# SPI.net
KiCad netlist of a schematic drawn in EAGLE
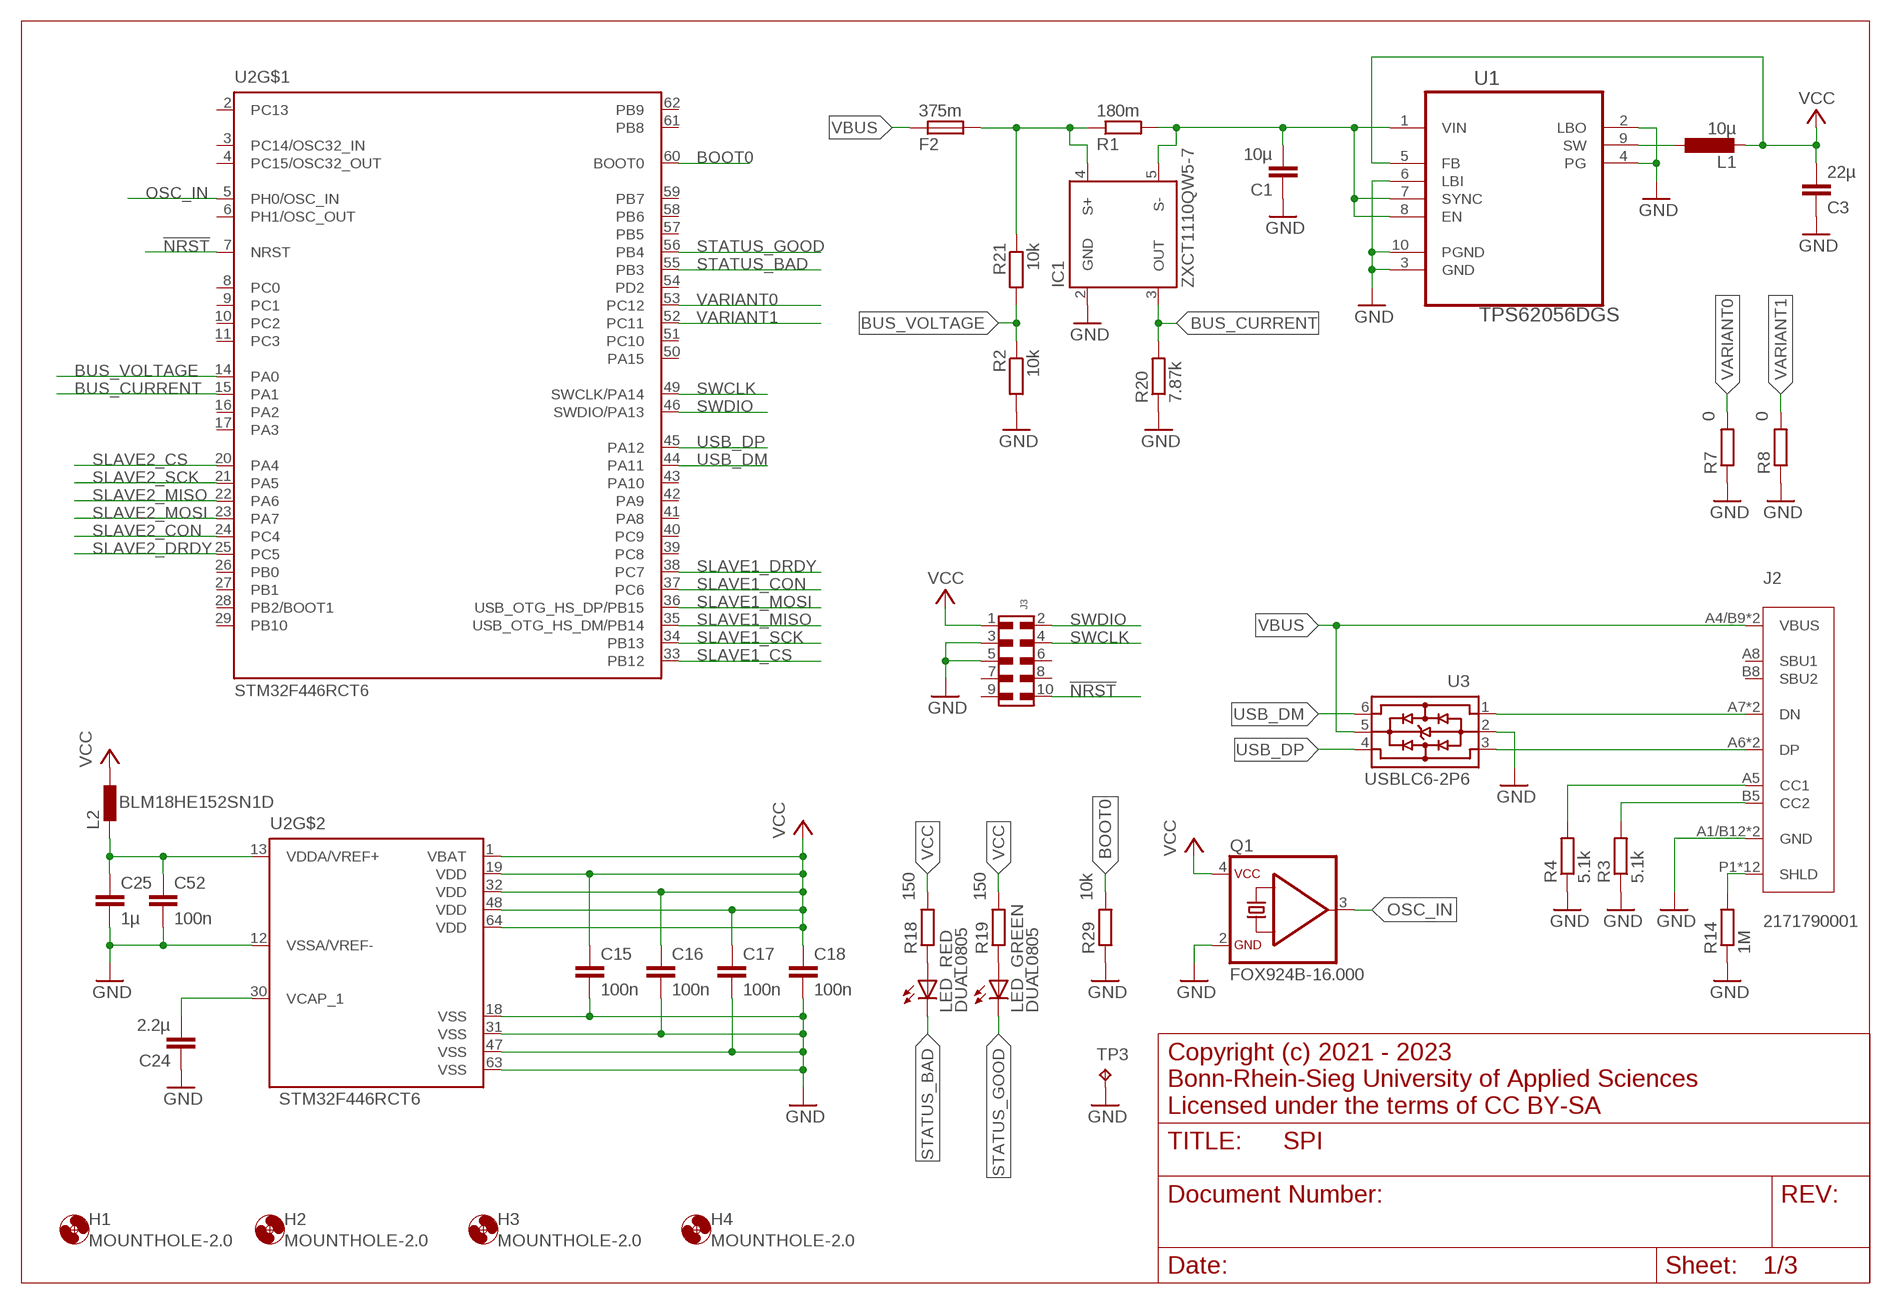
[diagram p0: schematic, sheet 1]
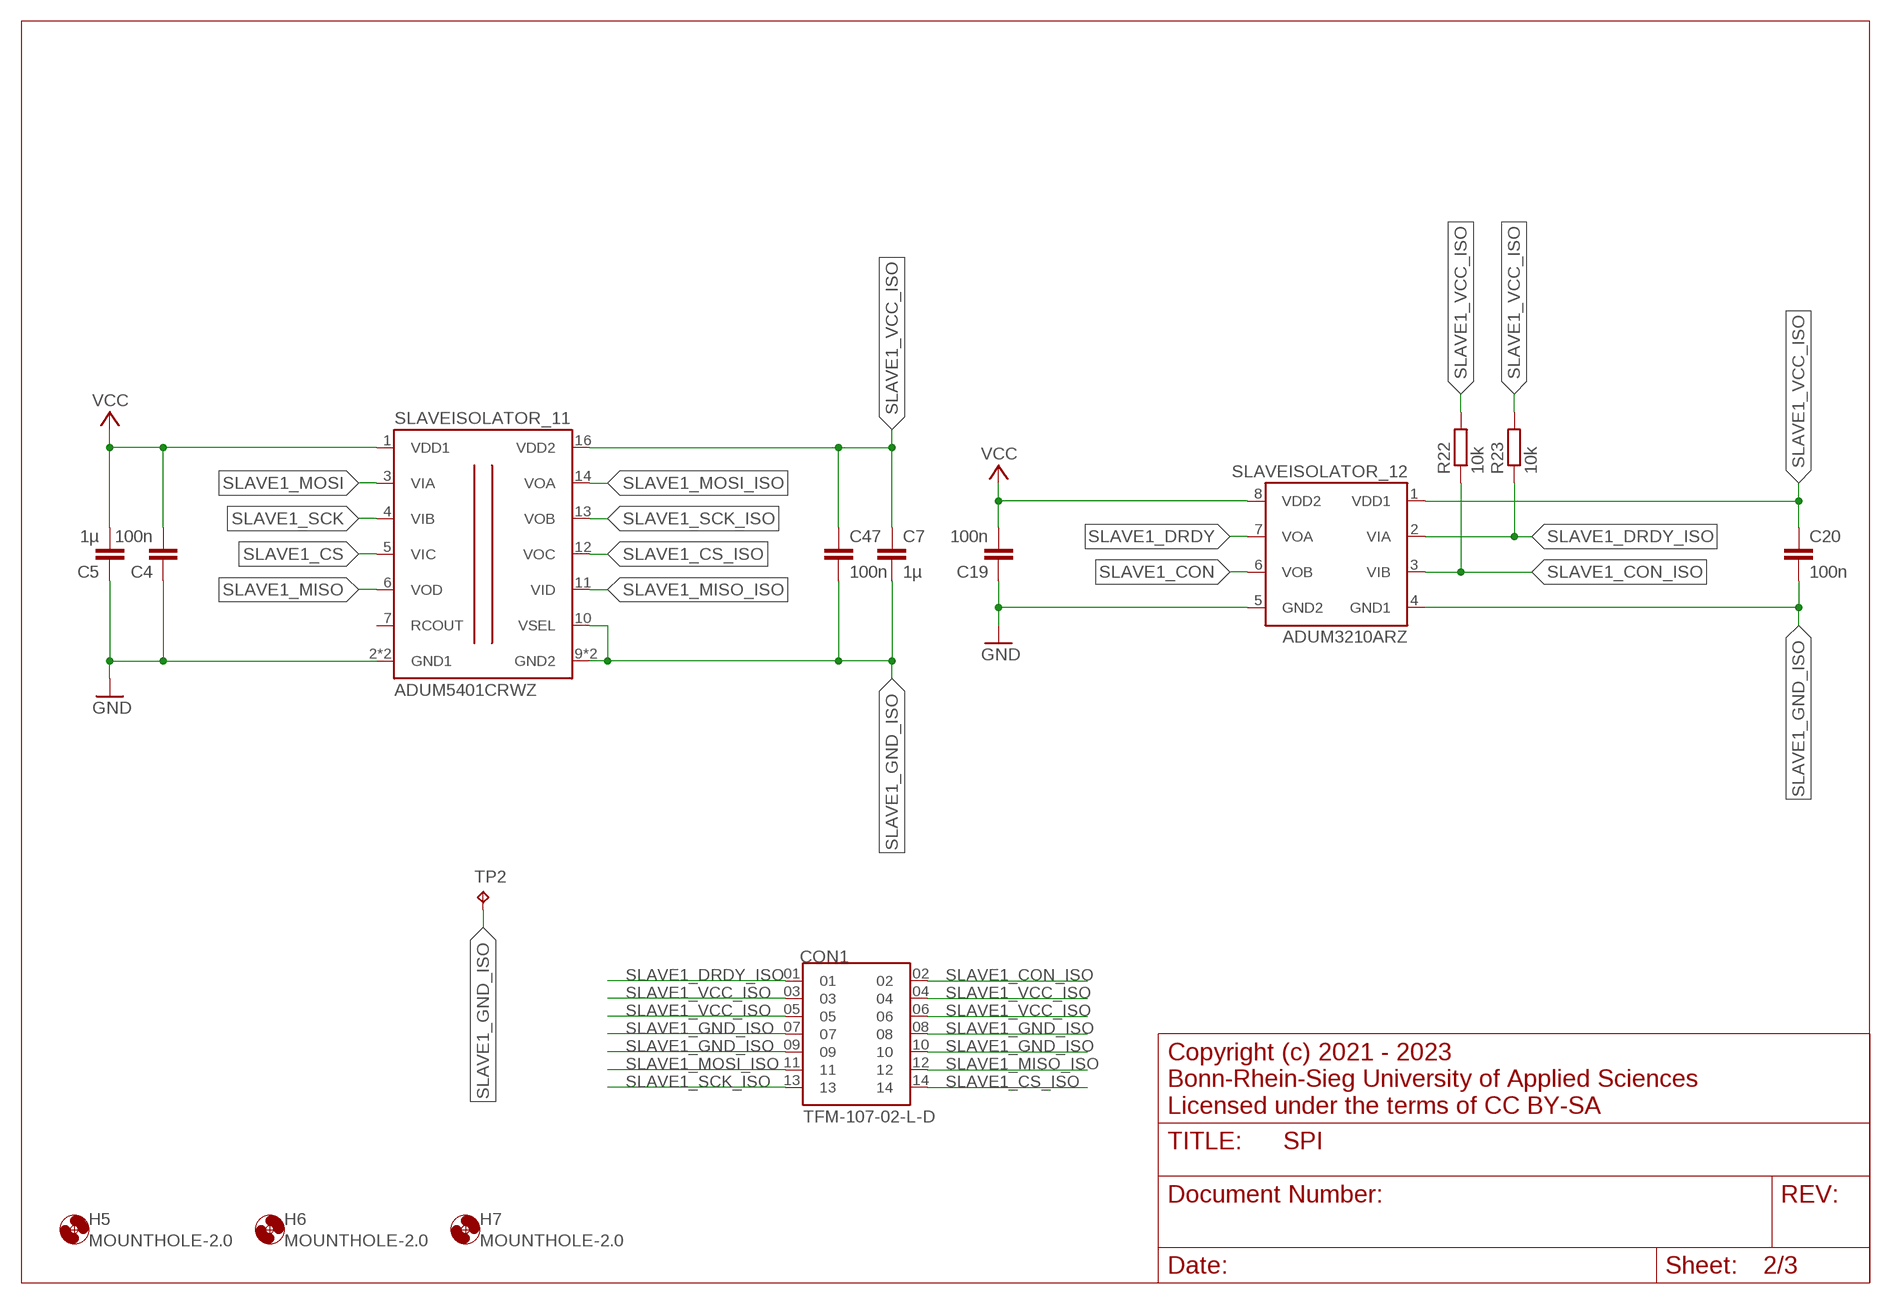
[diagram p1: schematic, sheet 2]
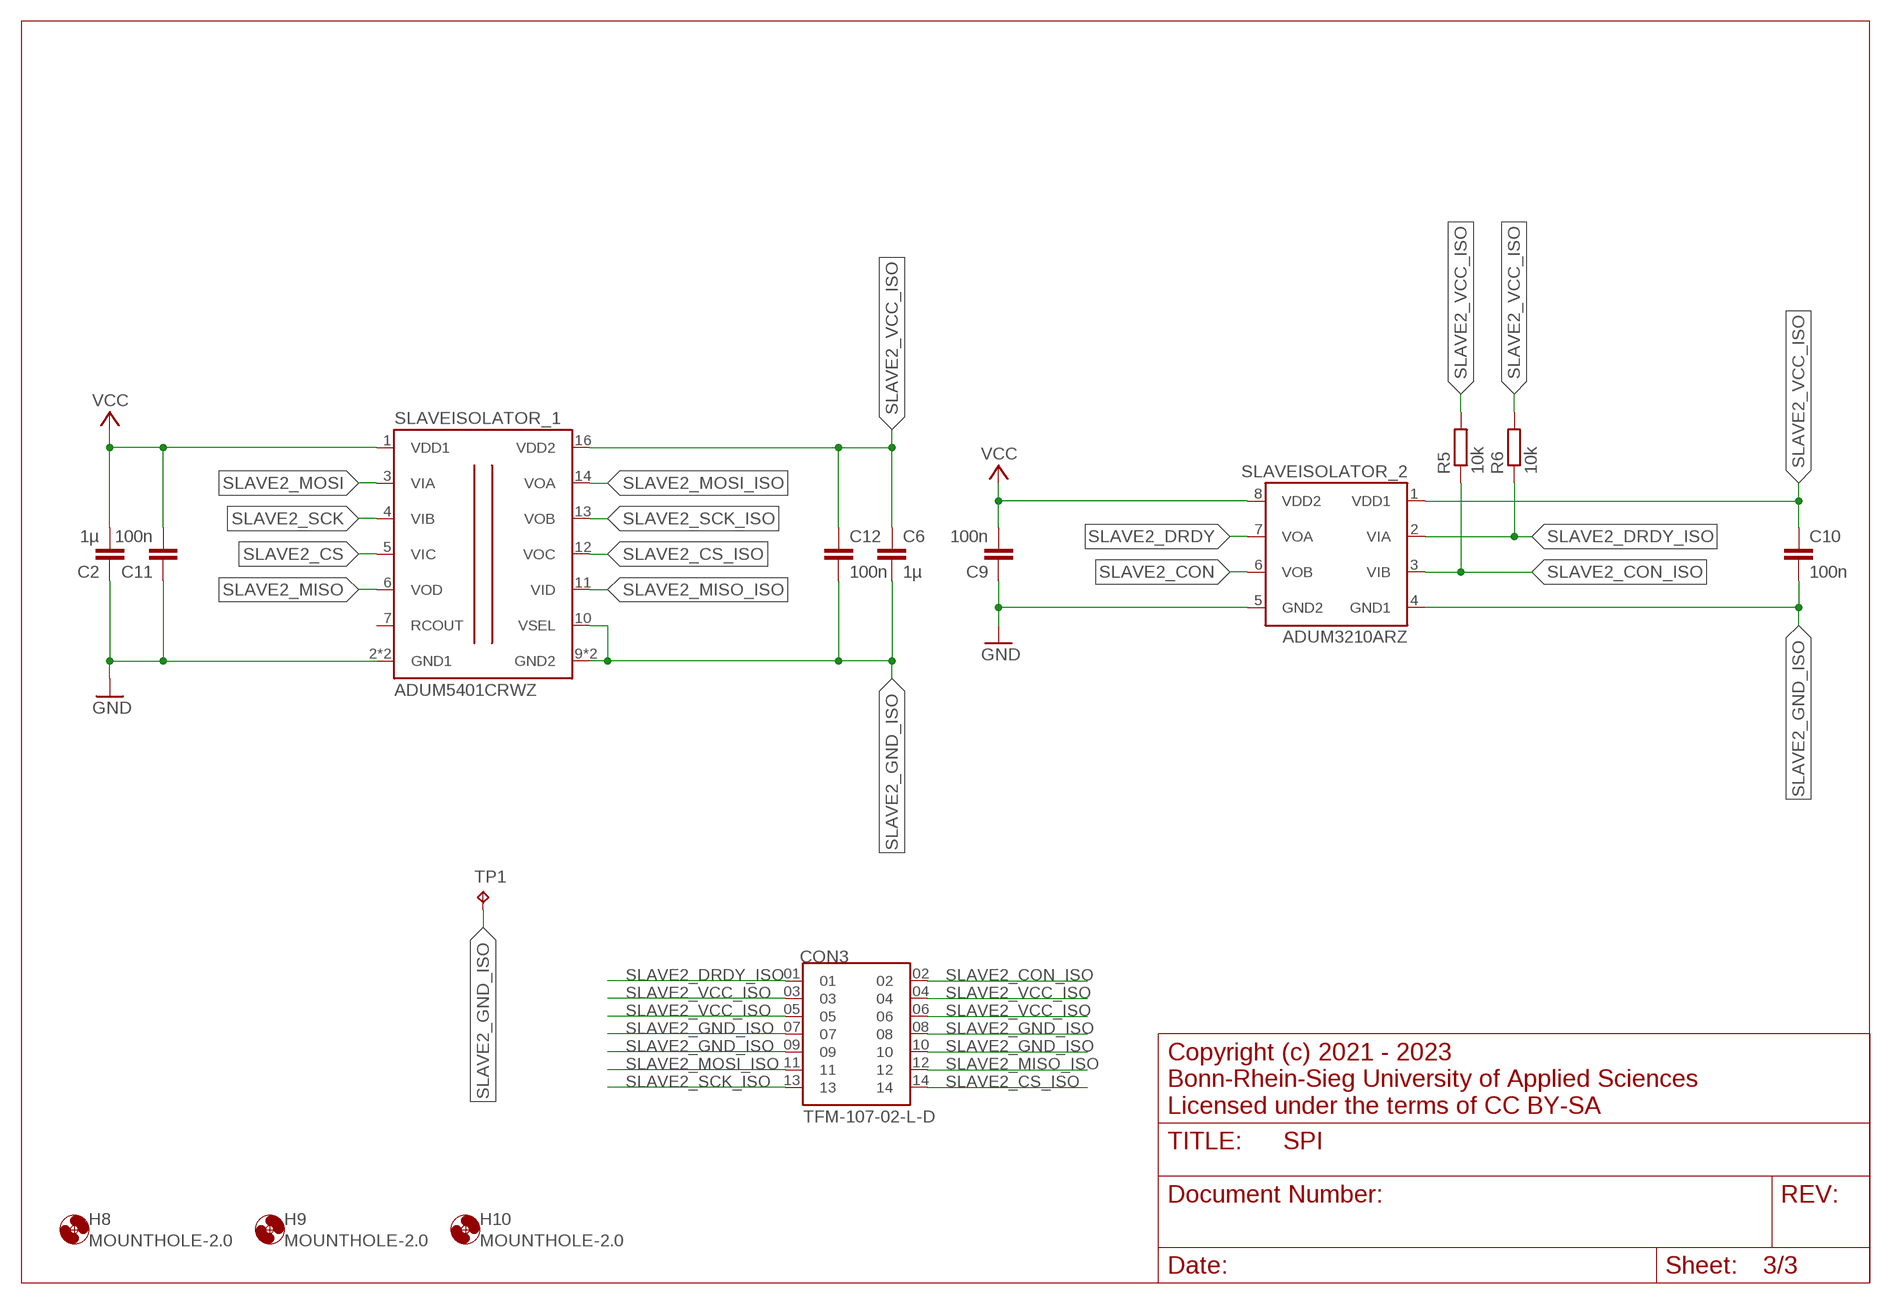
[diagram p2: schematic, sheet 3]

(export (version "E")
  (design (tool "Eeschema 10.0.6"))
  (components
    (comp (ref "C2")
      (value "1µ")
      (footprint "eagle-import:C0603")
      (libsource (lib "eagle-import") (part "C-EUC0603"))
    )
    (comp (ref "C6")
      (value "1µ")
      (footprint "eagle-import:C0603")
      (libsource (lib "eagle-import") (part "C-EUC0603"))
    )
    (comp (ref "C9")
      (value "100n")
      (footprint "eagle-import:C0603")
      (libsource (lib "eagle-import") (part "C-EUC0603"))
    )
    (comp (ref "C10")
      (value "100n")
      (footprint "eagle-import:C0603")
      (libsource (lib "eagle-import") (part "C-EUC0603"))
    )
    (comp (ref "C11")
      (value "100n")
      (footprint "eagle-import:C0603")
      (libsource (lib "eagle-import") (part "C-EUC0603"))
    )
    (comp (ref "C12")
      (value "100n")
      (footprint "eagle-import:C0603")
      (libsource (lib "eagle-import") (part "C-EUC0603"))
    )
    (comp (ref "CON3")
      (value "TFM-107-02-L-D")
      (footprint "eagle-import:SAMTEC_TFM-107-02-L-D")
      (fields (field (name "DIGI-KEY_PART_NUMBER") "SAM14682TR-ND") (field (name "MF") "Samtec"))
      (libsource (lib "eagle-import") (part "TFM-107-02-L-D"))
    )
    (comp (ref "H8")
      (value "MOUNTHOLE-2.0")
      (footprint "eagle-import:2.0")
      (libsource (lib "eagle-import") (part "MOUNTHOLE-2.0"))
    )
    (comp (ref "H9")
      (value "MOUNTHOLE-2.0")
      (footprint "eagle-import:2.0")
      (libsource (lib "eagle-import") (part "MOUNTHOLE-2.0"))
    )
    (comp (ref "H10")
      (value "MOUNTHOLE-2.0")
      (footprint "eagle-import:2.0")
      (libsource (lib "eagle-import") (part "MOUNTHOLE-2.0"))
    )
    (comp (ref "R5")
      (value "10k")
      (footprint "eagle-import:R0603")
      (libsource (lib "eagle-import") (part "R-EU_R0603"))
    )
    (comp (ref "R6")
      (value "10k")
      (footprint "eagle-import:R0603")
      (libsource (lib "eagle-import") (part "R-EU_R0603"))
    )
    (comp (ref "SLAVEISOLATOR_1")
      (value "ADUM5401CRWZ")
      (footprint "eagle-import:SO16W")
      (libsource (lib "eagle-import") (part "ADUM5401RWZC"))
    )
    (comp (ref "SLAVEISOLATOR_2")
      (value "ADUM3210ARZ")
      (footprint "eagle-import:SOIC8")
      (libsource (lib "eagle-import") (part "ADUM3210RZA"))
    )
    (comp (ref "TP1")
      (value "TP3.8X2.03")
      (footprint "eagle-import:3.8X2.03")
      (libsource (lib "eagle-import") (part "TP3.8X2.03"))
    )
    (comp (ref "C1")
      (value "10µ")
      (footprint "eagle-import:C0603")
      (libsource (lib "eagle-import") (part "rcl_334_C-EUC0603"))
    )
    (comp (ref "C3")
      (value "22µ")
      (footprint "eagle-import:C0603")
      (libsource (lib "eagle-import") (part "rcl_334_C-EUC0603"))
    )
    (comp (ref "C15")
      (value "100n")
      (footprint "eagle-import:C0603")
      (libsource (lib "eagle-import") (part "C-EUC0603"))
    )
    (comp (ref "C16")
      (value "100n")
      (footprint "eagle-import:C0603")
      (libsource (lib "eagle-import") (part "C-EUC0603"))
    )
    (comp (ref "C17")
      (value "100n")
      (footprint "eagle-import:C0603")
      (libsource (lib "eagle-import") (part "C-EUC0603"))
    )
    (comp (ref "C18")
      (value "100n")
      (footprint "eagle-import:C0603")
      (libsource (lib "eagle-import") (part "C-EUC0603"))
    )
    (comp (ref "C24")
      (value "2.2µ")
      (footprint "eagle-import:C0603")
      (libsource (lib "eagle-import") (part "C-EUC0603"))
    )
    (comp (ref "C25")
      (value "1µ")
      (footprint "eagle-import:C0603")
      (libsource (lib "eagle-import") (part "C-EUC0603"))
    )
    (comp (ref "C52")
      (value "100n")
      (footprint "eagle-import:C0603")
      (libsource (lib "eagle-import") (part "C-EUC0603"))
    )
    (comp (ref "F2")
      (value "375m")
      (footprint "eagle-import:R0603")
      (libsource (lib "eagle-import") (part "FUSE0603"))
    )
    (comp (ref "H1")
      (value "MOUNTHOLE-2.0")
      (footprint "eagle-import:2.0")
      (libsource (lib "eagle-import") (part "MOUNTHOLE-2.0"))
    )
    (comp (ref "H2")
      (value "MOUNTHOLE-2.0")
      (footprint "eagle-import:2.0")
      (libsource (lib "eagle-import") (part "MOUNTHOLE-2.0"))
    )
    (comp (ref "H3")
      (value "MOUNTHOLE-2.0")
      (footprint "eagle-import:2.0")
      (libsource (lib "eagle-import") (part "MOUNTHOLE-2.0"))
    )
    (comp (ref "H4")
      (value "MOUNTHOLE-2.0")
      (footprint "eagle-import:2.0")
      (libsource (lib "eagle-import") (part "MOUNTHOLE-2.0"))
    )
    (comp (ref "IC1")
      (value "ZXCT1110QW5-7")
      (footprint "eagle-import:SOT23-5L")
      (libsource (lib "eagle-import") (part "ZXCT1110QW5-7"))
    )
    (comp (ref "J2")
      (value "2171790001")
      (footprint "eagle-import:2171790001_MOL")
      (fields (field (name "COPYRIGHT") "Copyright (C) 2021 Ultra Librarian. All rights reserved."))
      (libsource (lib "eagle-import") (part "2171790001"))
    )
    (comp (ref "J3")
      (value "6210XX21021_62101021021")
      (footprint "eagle-import:62101021021")
      (libsource (lib "eagle-import") (part "6210XX21021_62101021021"))
    )
    (comp (ref "L1")
      (value "10µ")
      (footprint "eagle-import:2SMD")
      (libsource (lib "eagle-import") (part "VLS3012E?-T100M"))
    )
    (comp (ref "L2")
      (value "BLM18HE152SN1D")
      (footprint "eagle-import:0603")
      (libsource (lib "eagle-import") (part "BLM18HE152SN1D"))
    )
    (comp (ref "LED_")
      (value "DUAL0805")
      (footprint "eagle-import:CHIPLEDX2")
      (libsource (lib "eagle-import") (part "DUAL0805"))
    )
    (comp (ref "Q1")
      (value "FOX924B-16.000")
      (footprint "eagle-import:FOX924B")
      (libsource (lib "eagle-import") (part "FOX924B-16.000"))
    )
    (comp (ref "R1")
      (value "180m")
      (footprint "eagle-import:R0603")
      (libsource (lib "eagle-import") (part "rcl_334_R-EU_R0603"))
    )
    (comp (ref "R2")
      (value "10k")
      (footprint "eagle-import:R0603")
      (libsource (lib "eagle-import") (part "rcl_334_R-EU_R0603"))
    )
    (comp (ref "R3")
      (value "5.1k")
      (footprint "eagle-import:R0603")
      (libsource (lib "eagle-import") (part "rcl_334_R-EU_R0603"))
    )
    (comp (ref "R4")
      (value "5.1k")
      (footprint "eagle-import:R0603")
      (libsource (lib "eagle-import") (part "rcl_334_R-EU_R0603"))
    )
    (comp (ref "R7")
      (value "0")
      (footprint "eagle-import:R0603")
      (libsource (lib "eagle-import") (part "R-EU_R0603"))
    )
    (comp (ref "R8")
      (value "0")
      (footprint "eagle-import:R0603")
      (libsource (lib "eagle-import") (part "R-EU_R0603"))
    )
    (comp (ref "R14")
      (value "1M")
      (footprint "eagle-import:R0603")
      (libsource (lib "eagle-import") (part "rcl_334_R-EU_R0603"))
    )
    (comp (ref "R18")
      (value "150")
      (footprint "eagle-import:R0603")
      (libsource (lib "eagle-import") (part "R-EU_R0603"))
    )
    (comp (ref "R19")
      (value "150")
      (footprint "eagle-import:R0603")
      (libsource (lib "eagle-import") (part "R-EU_R0603"))
    )
    (comp (ref "R20")
      (value "7.87k")
      (footprint "eagle-import:R0603")
      (libsource (lib "eagle-import") (part "rcl_334_R-EU_R0603"))
    )
    (comp (ref "R21")
      (value "10k")
      (footprint "eagle-import:R0603")
      (libsource (lib "eagle-import") (part "rcl_334_R-EU_R0603"))
    )
    (comp (ref "R29")
      (value "10k")
      (footprint "eagle-import:R0603")
      (libsource (lib "eagle-import") (part "R-EU_R0603"))
    )
    (comp (ref "TP3")
      (value "TP3.8X2.03")
      (footprint "eagle-import:3.8X2.03")
      (libsource (lib "eagle-import") (part "TP3.8X2.03"))
    )
    (comp (ref "U1")
      (value "TPS62056DGS")
      (footprint "eagle-import:SOP50P490X110-10N")
      (libsource (lib "eagle-import") (part "TPS62056DGS"))
    )
    (comp (ref "U2")
      (value "STM32F446RCT6")
      (footprint "eagle-import:LQFP64")
      (libsource (lib "eagle-import") (part "STM32F446R?T6C"))
    )
    (comp (ref "U3")
      (value "USBLC6-2P6")
      (footprint "eagle-import:SOT-666")
      (libsource (lib "eagle-import") (part "USBLC6-2P6"))
    )
    (comp (ref "C4")
      (value "100n")
      (footprint "eagle-import:C0603")
      (libsource (lib "eagle-import") (part "C-EUC0603"))
    )
    (comp (ref "C5")
      (value "1µ")
      (footprint "eagle-import:C0603")
      (libsource (lib "eagle-import") (part "C-EUC0603"))
    )
    (comp (ref "C7")
      (value "1µ")
      (footprint "eagle-import:C0603")
      (libsource (lib "eagle-import") (part "C-EUC0603"))
    )
    (comp (ref "C19")
      (value "100n")
      (footprint "eagle-import:C0603")
      (libsource (lib "eagle-import") (part "C-EUC0603"))
    )
    (comp (ref "C20")
      (value "100n")
      (footprint "eagle-import:C0603")
      (libsource (lib "eagle-import") (part "C-EUC0603"))
    )
    (comp (ref "C47")
      (value "100n")
      (footprint "eagle-import:C0603")
      (libsource (lib "eagle-import") (part "C-EUC0603"))
    )
    (comp (ref "CON1")
      (value "TFM-107-02-L-D")
      (footprint "eagle-import:SAMTEC_TFM-107-02-L-D")
      (fields (field (name "DIGI-KEY_PART_NUMBER") "SAM14682TR-ND") (field (name "MF") "Samtec"))
      (libsource (lib "eagle-import") (part "TFM-107-02-L-D"))
    )
    (comp (ref "H5")
      (value "MOUNTHOLE-2.0")
      (footprint "eagle-import:2.0")
      (libsource (lib "eagle-import") (part "MOUNTHOLE-2.0"))
    )
    (comp (ref "H6")
      (value "MOUNTHOLE-2.0")
      (footprint "eagle-import:2.0")
      (libsource (lib "eagle-import") (part "MOUNTHOLE-2.0"))
    )
    (comp (ref "H7")
      (value "MOUNTHOLE-2.0")
      (footprint "eagle-import:2.0")
      (libsource (lib "eagle-import") (part "MOUNTHOLE-2.0"))
    )
    (comp (ref "R22")
      (value "10k")
      (footprint "eagle-import:R0603")
      (libsource (lib "eagle-import") (part "R-EU_R0603"))
    )
    (comp (ref "R23")
      (value "10k")
      (footprint "eagle-import:R0603")
      (libsource (lib "eagle-import") (part "R-EU_R0603"))
    )
    (comp (ref "SLAVEISOLATOR_11")
      (value "ADUM5401CRWZ")
      (footprint "eagle-import:SO16W")
      (libsource (lib "eagle-import") (part "ADUM5401RWZC"))
    )
    (comp (ref "SLAVEISOLATOR_12")
      (value "ADUM3210ARZ")
      (footprint "eagle-import:SOIC8")
      (libsource (lib "eagle-import") (part "ADUM3210RZA"))
    )
    (comp (ref "TP2")
      (value "TP3.8X2.03")
      (footprint "eagle-import:3.8X2.03")
      (libsource (lib "eagle-import") (part "TP3.8X2.03"))
    )
  )
  (nets
    (net (code "1") (name "BOOT0") (class "Default")
      (node (ref "R29") (pin "2") (pinfunction "2_2") (pintype "passive"))
      (node (ref "U2") (pin "60") (pinfunction "BOOT0_60") (pintype "bidirectional"))
    )
    (net (code "2") (name "BUS_CURRENT") (class "Default")
      (node (ref "IC1") (pin "3") (pinfunction "OUT_3") (pintype "output"))
      (node (ref "R20") (pin "2") (pinfunction "2_2") (pintype "passive"))
      (node (ref "U2") (pin "15") (pinfunction "PA1_15") (pintype "bidirectional"))
    )
    (net (code "3") (name "BUS_VOLTAGE") (class "Default")
      (node (ref "R2") (pin "1") (pinfunction "1_1") (pintype "passive"))
      (node (ref "R21") (pin "2") (pinfunction "2_2") (pintype "passive"))
      (node (ref "U2") (pin "14") (pinfunction "PA0_14") (pintype "bidirectional"))
    )
    (net (code "4") (name "GND") (class "Default")
      (node (ref "C1") (pin "1") (pinfunction "1_1") (pintype "passive"))
      (node (ref "C11") (pin "1") (pinfunction "1_1") (pintype "passive"))
      (node (ref "C15") (pin "2") (pinfunction "2_2") (pintype "passive"))
      (node (ref "C16") (pin "2") (pinfunction "2_2") (pintype "passive"))
      (node (ref "C17") (pin "2") (pinfunction "2_2") (pintype "passive"))
      (node (ref "C18") (pin "2") (pinfunction "2_2") (pintype "passive"))
      (node (ref "C19") (pin "1") (pinfunction "1_1") (pintype "passive"))
      (node (ref "C2") (pin "1") (pinfunction "1_1") (pintype "passive"))
      (node (ref "C24") (pin "1") (pinfunction "1_1") (pintype "passive"))
      (node (ref "C25") (pin "2") (pinfunction "2_2") (pintype "passive"))
      (node (ref "C3") (pin "1") (pinfunction "1_1") (pintype "passive"))
      (node (ref "C4") (pin "1") (pinfunction "1_1") (pintype "passive"))
      (node (ref "C5") (pin "1") (pinfunction "1_1") (pintype "passive"))
      (node (ref "C52") (pin "2") (pinfunction "2_2") (pintype "passive"))
      (node (ref "C9") (pin "1") (pinfunction "1_1") (pintype "passive"))
      (node (ref "IC1") (pin "2") (pinfunction "GND_2") (pintype "power_in"))
      (node (ref "J2") (pin "A1/B12") (pinfunction "GND_A1/B12") (pintype "passive"))
      (node (ref "J2") (pin "B1/A12") (pinfunction "GND_B1/A12") (pintype "passive"))
      (node (ref "J3") (pin "3") (pinfunction "3_3") (pintype "passive"))
      (node (ref "J3") (pin "5") (pinfunction "5_5") (pintype "passive"))
      (node (ref "Q1") (pin "2") (pinfunction "GND_2") (pintype "power_in"))
      (node (ref "R14") (pin "1") (pinfunction "1_1") (pintype "passive"))
      (node (ref "R2") (pin "2") (pinfunction "2_2") (pintype "passive"))
      (node (ref "R20") (pin "1") (pinfunction "1_1") (pintype "passive"))
      (node (ref "R29") (pin "1") (pinfunction "1_1") (pintype "passive"))
      (node (ref "R3") (pin "1") (pinfunction "1_1") (pintype "passive"))
      (node (ref "R4") (pin "1") (pinfunction "1_1") (pintype "passive"))
      (node (ref "R7") (pin "1") (pinfunction "1_1") (pintype "passive"))
      (node (ref "R8") (pin "1") (pinfunction "1_1") (pintype "passive"))
      (node (ref "SLAVEISOLATOR_1") (pin "2") (pinfunction "GND1_2") (pintype "bidirectional"))
      (node (ref "SLAVEISOLATOR_1") (pin "8") (pinfunction "GND1_8") (pintype "bidirectional"))
      (node (ref "SLAVEISOLATOR_11") (pin "2") (pinfunction "GND1_2") (pintype "bidirectional"))
      (node (ref "SLAVEISOLATOR_11") (pin "8") (pinfunction "GND1_8") (pintype "bidirectional"))
      (node (ref "SLAVEISOLATOR_12") (pin "5") (pinfunction "GND2_5") (pintype "bidirectional"))
      (node (ref "SLAVEISOLATOR_2") (pin "5") (pinfunction "GND2_5") (pintype "bidirectional"))
      (node (ref "TP3") (pin "TP") (pinfunction "TP_TP") (pintype "input"))
      (node (ref "U1") (pin "10") (pinfunction "PGND_10") (pintype "passive"))
      (node (ref "U1") (pin "2") (pinfunction "LBO_2") (pintype "bidirectional"))
      (node (ref "U1") (pin "3") (pinfunction "GND_3") (pintype "passive"))
      (node (ref "U1") (pin "4") (pinfunction "PG_4") (pintype "bidirectional"))
      (node (ref "U1") (pin "6") (pinfunction "LBI_6") (pintype "input"))
      (node (ref "U2") (pin "12") (pinfunction "VSSA/VREF-_12") (pintype "bidirectional"))
      (node (ref "U2") (pin "18") (pinfunction "VSS_18") (pintype "bidirectional"))
      (node (ref "U2") (pin "31") (pinfunction "VSS_31") (pintype "bidirectional"))
      (node (ref "U2") (pin "47") (pinfunction "VSS_47") (pintype "bidirectional"))
      (node (ref "U2") (pin "63") (pinfunction "VSS_63") (pintype "bidirectional"))
      (node (ref "U3") (pin "2") (pinfunction "2_2") (pintype "passive"))
    )
    (net (code "5") (name "Net-(IC1-S+)") (class "Default")
      (node (ref "F2") (pin "2") (pinfunction "2_2") (pintype "passive"))
      (node (ref "IC1") (pin "4") (pinfunction "S+_4") (pintype "input"))
      (node (ref "R1") (pin "1") (pinfunction "1_1") (pintype "passive"))
      (node (ref "R21") (pin "1") (pinfunction "1_1") (pintype "passive"))
    )
    (net (code "6") (name "Net-(IC1-S-)") (class "Default")
      (node (ref "C1") (pin "2") (pinfunction "2_2") (pintype "passive"))
      (node (ref "IC1") (pin "5") (pinfunction "S-_5") (pintype "input"))
      (node (ref "R1") (pin "2") (pinfunction "2_2") (pintype "passive"))
      (node (ref "U1") (pin "1") (pinfunction "VIN_1") (pintype "power_in"))
      (node (ref "U1") (pin "7") (pinfunction "SYNC_7") (pintype "input"))
      (node (ref "U1") (pin "8") (pinfunction "EN_8") (pintype "input"))
    )
    (net (code "7") (name "Net-(J2-CC1)") (class "Default")
      (node (ref "J2") (pin "A5") (pinfunction "CC1_A5") (pintype "bidirectional"))
      (node (ref "R4") (pin "2") (pinfunction "2_2") (pintype "passive"))
    )
    (net (code "8") (name "Net-(J2-CC2)") (class "Default")
      (node (ref "J2") (pin "B5") (pinfunction "CC2_B5") (pintype "bidirectional"))
      (node (ref "R3") (pin "2") (pinfunction "2_2") (pintype "passive"))
    )
    (net (code "9") (name "Net-(J2-DN-PadA7)") (class "Default")
      (node (ref "J2") (pin "A7") (pinfunction "DN_A7") (pintype "bidirectional"))
      (node (ref "J2") (pin "B7") (pinfunction "DN_B7") (pintype "bidirectional"))
      (node (ref "U3") (pin "1") (pinfunction "1_1") (pintype "bidirectional"))
    )
    (net (code "10") (name "Net-(J2-DP-PadA6)") (class "Default")
      (node (ref "J2") (pin "A6") (pinfunction "DP_A6") (pintype "bidirectional"))
      (node (ref "J2") (pin "B6") (pinfunction "DP_B6") (pintype "bidirectional"))
      (node (ref "U3") (pin "3") (pinfunction "3_3") (pintype "bidirectional"))
    )
    (net (code "11") (name "Net-(J2-SHLD-PadP1)") (class "Default")
      (node (ref "J2") (pin "P1") (pinfunction "SHLD_P1") (pintype "bidirectional"))
      (node (ref "J2") (pin "P2") (pinfunction "SHLD_P2") (pintype "bidirectional"))
      (node (ref "J2") (pin "P3") (pinfunction "SHLD_P3") (pintype "bidirectional"))
      (node (ref "J2") (pin "P4") (pinfunction "SHLD_P4") (pintype "bidirectional"))
      (node (ref "J2") (pin "S1") (pinfunction "SHLD_S1") (pintype "bidirectional"))
      (node (ref "J2") (pin "S2") (pinfunction "SHLD_S2") (pintype "bidirectional"))
      (node (ref "J2") (pin "S3") (pinfunction "SHLD_S3") (pintype "bidirectional"))
      (node (ref "J2") (pin "S4") (pinfunction "SHLD_S4") (pintype "bidirectional"))
      (node (ref "J2") (pin "S5") (pinfunction "SHLD_S5") (pintype "bidirectional"))
      (node (ref "J2") (pin "S6") (pinfunction "SHLD_S6") (pintype "bidirectional"))
      (node (ref "J2") (pin "S7") (pinfunction "SHLD_S7") (pintype "bidirectional"))
      (node (ref "J2") (pin "S8") (pinfunction "SHLD_S8") (pintype "bidirectional"))
      (node (ref "R14") (pin "2") (pinfunction "2_2") (pintype "passive"))
    )
    (net (code "12") (name "Net-(L1-1)") (class "Default")
      (node (ref "L1") (pin "P$1") (pinfunction "1_P$1") (pintype "passive"))
      (node (ref "U1") (pin "9") (pinfunction "SW_9") (pintype "output"))
    )
    (net (code "13") (name "Net-(LED_A-A)") (class "Default")
      (node (ref "LED_") (pin "A2") (pinfunction "A_A2") (pintype "passive"))
      (node (ref "R19") (pin "1") (pinfunction "1_1") (pintype "passive"))
    )
    (net (code "14") (name "Net-(LED_B-A)") (class "Default")
      (node (ref "LED_") (pin "A1") (pinfunction "A_A1") (pintype "passive"))
      (node (ref "R18") (pin "1") (pinfunction "1_1") (pintype "passive"))
    )
    (net (code "15") (name "Net-(U2B-VCAP_1)") (class "Default")
      (node (ref "C24") (pin "2") (pinfunction "2_2") (pintype "passive"))
      (node (ref "U2") (pin "30") (pinfunction "VCAP_1_30") (pintype "bidirectional"))
    )
    (net (code "16") (name "Net-(U2B-VDDA{slash}VREF+)") (class "Default")
      (node (ref "C25") (pin "1") (pinfunction "1_1") (pintype "passive"))
      (node (ref "C52") (pin "1") (pinfunction "1_1") (pintype "passive"))
      (node (ref "L2") (pin "2") (pinfunction "2_2") (pintype "passive"))
      (node (ref "U2") (pin "13") (pinfunction "VDDA/VREF+_13") (pintype "bidirectional"))
    )
    (net (code "17") (name "OSC_IN") (class "Default")
      (node (ref "Q1") (pin "3") (pinfunction "OUT_3") (pintype "output"))
      (node (ref "U2") (pin "5") (pinfunction "PH0/OSC_IN_5") (pintype "bidirectional"))
    )
    (net (code "18") (name "SLAVE1_CON") (class "Default")
      (node (ref "SLAVEISOLATOR_12") (pin "6") (pinfunction "VOB_6") (pintype "bidirectional"))
      (node (ref "U2") (pin "37") (pinfunction "PC6_37") (pintype "bidirectional"))
    )
    (net (code "19") (name "SLAVE1_CON_ISO") (class "Default")
      (node (ref "CON1") (pin "02") (pinfunction "02_02") (pintype "passive"))
      (node (ref "R22") (pin "1") (pinfunction "1_1") (pintype "passive"))
      (node (ref "SLAVEISOLATOR_12") (pin "3") (pinfunction "VIB_3") (pintype "bidirectional"))
    )
    (net (code "20") (name "SLAVE1_CS") (class "Default")
      (node (ref "SLAVEISOLATOR_11") (pin "5") (pinfunction "VIC_5") (pintype "bidirectional"))
      (node (ref "U2") (pin "33") (pinfunction "PB12_33") (pintype "bidirectional"))
    )
    (net (code "21") (name "SLAVE1_CS_ISO") (class "Default")
      (node (ref "CON1") (pin "14") (pinfunction "14_14") (pintype "passive"))
      (node (ref "SLAVEISOLATOR_11") (pin "12") (pinfunction "VOC_12") (pintype "bidirectional"))
    )
    (net (code "22") (name "SLAVE1_DRDY") (class "Default")
      (node (ref "SLAVEISOLATOR_12") (pin "7") (pinfunction "VOA_7") (pintype "bidirectional"))
      (node (ref "U2") (pin "38") (pinfunction "PC7_38") (pintype "bidirectional"))
    )
    (net (code "23") (name "SLAVE1_DRDY_ISO") (class "Default")
      (node (ref "CON1") (pin "01") (pinfunction "01_01") (pintype "passive"))
      (node (ref "R23") (pin "1") (pinfunction "1_1") (pintype "passive"))
      (node (ref "SLAVEISOLATOR_12") (pin "2") (pinfunction "VIA_2") (pintype "bidirectional"))
    )
    (net (code "24") (name "SLAVE1_GND_ISO") (class "Default")
      (node (ref "C20") (pin "2") (pinfunction "2_2") (pintype "passive"))
      (node (ref "C47") (pin "2") (pinfunction "2_2") (pintype "passive"))
      (node (ref "C7") (pin "2") (pinfunction "2_2") (pintype "passive"))
      (node (ref "CON1") (pin "07") (pinfunction "07_07") (pintype "passive"))
      (node (ref "CON1") (pin "08") (pinfunction "08_08") (pintype "passive"))
      (node (ref "CON1") (pin "09") (pinfunction "09_09") (pintype "passive"))
      (node (ref "CON1") (pin "10") (pinfunction "10_10") (pintype "passive"))
      (node (ref "SLAVEISOLATOR_11") (pin "10") (pinfunction "VSEL_10") (pintype "bidirectional"))
      (node (ref "SLAVEISOLATOR_11") (pin "15") (pinfunction "GND2_15") (pintype "bidirectional"))
      (node (ref "SLAVEISOLATOR_11") (pin "9") (pinfunction "GND2_9") (pintype "bidirectional"))
      (node (ref "SLAVEISOLATOR_12") (pin "4") (pinfunction "GND1_4") (pintype "bidirectional"))
      (node (ref "TP2") (pin "TP") (pinfunction "TP_TP") (pintype "input"))
    )
    (net (code "25") (name "SLAVE1_MISO") (class "Default")
      (node (ref "SLAVEISOLATOR_11") (pin "6") (pinfunction "VOD_6") (pintype "bidirectional"))
      (node (ref "U2") (pin "35") (pinfunction "USB_OTG_HS_DM/PB14_35") (pintype "bidirectional"))
    )
    (net (code "26") (name "SLAVE1_MISO_ISO") (class "Default")
      (node (ref "CON1") (pin "12") (pinfunction "12_12") (pintype "passive"))
      (node (ref "SLAVEISOLATOR_11") (pin "11") (pinfunction "VID_11") (pintype "bidirectional"))
    )
    (net (code "27") (name "SLAVE1_MOSI") (class "Default")
      (node (ref "SLAVEISOLATOR_11") (pin "3") (pinfunction "VIA_3") (pintype "bidirectional"))
      (node (ref "U2") (pin "36") (pinfunction "USB_OTG_HS_DP/PB15_36") (pintype "bidirectional"))
    )
    (net (code "28") (name "SLAVE1_MOSI_ISO") (class "Default")
      (node (ref "CON1") (pin "11") (pinfunction "11_11") (pintype "passive"))
      (node (ref "SLAVEISOLATOR_11") (pin "14") (pinfunction "VOA_14") (pintype "bidirectional"))
    )
    (net (code "29") (name "SLAVE1_SCK") (class "Default")
      (node (ref "SLAVEISOLATOR_11") (pin "4") (pinfunction "VIB_4") (pintype "bidirectional"))
      (node (ref "U2") (pin "34") (pinfunction "PB13_34") (pintype "bidirectional"))
    )
    (net (code "30") (name "SLAVE1_SCK_ISO") (class "Default")
      (node (ref "CON1") (pin "13") (pinfunction "13_13") (pintype "passive"))
      (node (ref "SLAVEISOLATOR_11") (pin "13") (pinfunction "VOB_13") (pintype "bidirectional"))
    )
    (net (code "31") (name "SLAVE1_VCC_ISO") (class "Default")
      (node (ref "C20") (pin "1") (pinfunction "1_1") (pintype "passive"))
      (node (ref "C47") (pin "1") (pinfunction "1_1") (pintype "passive"))
      (node (ref "C7") (pin "1") (pinfunction "1_1") (pintype "passive"))
      (node (ref "CON1") (pin "03") (pinfunction "03_03") (pintype "passive"))
      (node (ref "CON1") (pin "04") (pinfunction "04_04") (pintype "passive"))
      (node (ref "CON1") (pin "05") (pinfunction "05_05") (pintype "passive"))
      (node (ref "CON1") (pin "06") (pinfunction "06_06") (pintype "passive"))
      (node (ref "R22") (pin "2") (pinfunction "2_2") (pintype "passive"))
      (node (ref "R23") (pin "2") (pinfunction "2_2") (pintype "passive"))
      (node (ref "SLAVEISOLATOR_11") (pin "16") (pinfunction "VDD2_16") (pintype "bidirectional"))
      (node (ref "SLAVEISOLATOR_12") (pin "1") (pinfunction "VDD1_1") (pintype "bidirectional"))
    )
    (net (code "32") (name "SLAVE2_CON") (class "Default")
      (node (ref "SLAVEISOLATOR_2") (pin "6") (pinfunction "VOB_6") (pintype "bidirectional"))
      (node (ref "U2") (pin "24") (pinfunction "PC4_24") (pintype "bidirectional"))
    )
    (net (code "33") (name "SLAVE2_CON_ISO") (class "Default")
      (node (ref "CON3") (pin "02") (pinfunction "02_02") (pintype "passive"))
      (node (ref "R5") (pin "1") (pinfunction "1_1") (pintype "passive"))
      (node (ref "SLAVEISOLATOR_2") (pin "3") (pinfunction "VIB_3") (pintype "bidirectional"))
    )
    (net (code "34") (name "SLAVE2_CS") (class "Default")
      (node (ref "SLAVEISOLATOR_1") (pin "5") (pinfunction "VIC_5") (pintype "bidirectional"))
      (node (ref "U2") (pin "20") (pinfunction "PA4_20") (pintype "bidirectional"))
    )
    (net (code "35") (name "SLAVE2_CS_ISO") (class "Default")
      (node (ref "CON3") (pin "14") (pinfunction "14_14") (pintype "passive"))
      (node (ref "SLAVEISOLATOR_1") (pin "12") (pinfunction "VOC_12") (pintype "bidirectional"))
    )
    (net (code "36") (name "SLAVE2_DRDY") (class "Default")
      (node (ref "SLAVEISOLATOR_2") (pin "7") (pinfunction "VOA_7") (pintype "bidirectional"))
      (node (ref "U2") (pin "25") (pinfunction "PC5_25") (pintype "bidirectional"))
    )
    (net (code "37") (name "SLAVE2_DRDY_ISO") (class "Default")
      (node (ref "CON3") (pin "01") (pinfunction "01_01") (pintype "passive"))
      (node (ref "R6") (pin "1") (pinfunction "1_1") (pintype "passive"))
      (node (ref "SLAVEISOLATOR_2") (pin "2") (pinfunction "VIA_2") (pintype "bidirectional"))
    )
    (net (code "38") (name "SLAVE2_GND_ISO") (class "Default")
      (node (ref "C10") (pin "2") (pinfunction "2_2") (pintype "passive"))
      (node (ref "C12") (pin "2") (pinfunction "2_2") (pintype "passive"))
      (node (ref "C6") (pin "2") (pinfunction "2_2") (pintype "passive"))
      (node (ref "CON3") (pin "07") (pinfunction "07_07") (pintype "passive"))
      (node (ref "CON3") (pin "08") (pinfunction "08_08") (pintype "passive"))
      (node (ref "CON3") (pin "09") (pinfunction "09_09") (pintype "passive"))
      (node (ref "CON3") (pin "10") (pinfunction "10_10") (pintype "passive"))
      (node (ref "SLAVEISOLATOR_1") (pin "10") (pinfunction "VSEL_10") (pintype "bidirectional"))
      (node (ref "SLAVEISOLATOR_1") (pin "15") (pinfunction "GND2_15") (pintype "bidirectional"))
      (node (ref "SLAVEISOLATOR_1") (pin "9") (pinfunction "GND2_9") (pintype "bidirectional"))
      (node (ref "SLAVEISOLATOR_2") (pin "4") (pinfunction "GND1_4") (pintype "bidirectional"))
      (node (ref "TP1") (pin "TP") (pinfunction "TP_TP") (pintype "input"))
    )
    (net (code "39") (name "SLAVE2_MISO") (class "Default")
      (node (ref "SLAVEISOLATOR_1") (pin "6") (pinfunction "VOD_6") (pintype "bidirectional"))
      (node (ref "U2") (pin "22") (pinfunction "PA6_22") (pintype "bidirectional"))
    )
    (net (code "40") (name "SLAVE2_MISO_ISO") (class "Default")
      (node (ref "CON3") (pin "12") (pinfunction "12_12") (pintype "passive"))
      (node (ref "SLAVEISOLATOR_1") (pin "11") (pinfunction "VID_11") (pintype "bidirectional"))
    )
    (net (code "41") (name "SLAVE2_MOSI") (class "Default")
      (node (ref "SLAVEISOLATOR_1") (pin "3") (pinfunction "VIA_3") (pintype "bidirectional"))
      (node (ref "U2") (pin "23") (pinfunction "PA7_23") (pintype "bidirectional"))
    )
    (net (code "42") (name "SLAVE2_MOSI_ISO") (class "Default")
      (node (ref "CON3") (pin "11") (pinfunction "11_11") (pintype "passive"))
      (node (ref "SLAVEISOLATOR_1") (pin "14") (pinfunction "VOA_14") (pintype "bidirectional"))
    )
    (net (code "43") (name "SLAVE2_SCK") (class "Default")
      (node (ref "SLAVEISOLATOR_1") (pin "4") (pinfunction "VIB_4") (pintype "bidirectional"))
      (node (ref "U2") (pin "21") (pinfunction "PA5_21") (pintype "bidirectional"))
    )
    (net (code "44") (name "SLAVE2_SCK_ISO") (class "Default")
      (node (ref "CON3") (pin "13") (pinfunction "13_13") (pintype "passive"))
      (node (ref "SLAVEISOLATOR_1") (pin "13") (pinfunction "VOB_13") (pintype "bidirectional"))
    )
    (net (code "45") (name "SLAVE2_VCC_ISO") (class "Default")
      (node (ref "C10") (pin "1") (pinfunction "1_1") (pintype "passive"))
      (node (ref "C12") (pin "1") (pinfunction "1_1") (pintype "passive"))
      (node (ref "C6") (pin "1") (pinfunction "1_1") (pintype "passive"))
      (node (ref "CON3") (pin "03") (pinfunction "03_03") (pintype "passive"))
      (node (ref "CON3") (pin "04") (pinfunction "04_04") (pintype "passive"))
      (node (ref "CON3") (pin "05") (pinfunction "05_05") (pintype "passive"))
      (node (ref "CON3") (pin "06") (pinfunction "06_06") (pintype "passive"))
      (node (ref "R5") (pin "2") (pinfunction "2_2") (pintype "passive"))
      (node (ref "R6") (pin "2") (pinfunction "2_2") (pintype "passive"))
      (node (ref "SLAVEISOLATOR_1") (pin "16") (pinfunction "VDD2_16") (pintype "bidirectional"))
      (node (ref "SLAVEISOLATOR_2") (pin "1") (pinfunction "VDD1_1") (pintype "bidirectional"))
    )
    (net (code "46") (name "STATUS_BAD") (class "Default")
      (node (ref "LED_") (pin "C1") (pinfunction "C_C1") (pintype "passive"))
      (node (ref "U2") (pin "55") (pinfunction "PB3_55") (pintype "bidirectional"))
    )
    (net (code "47") (name "STATUS_GOOD") (class "Default")
      (node (ref "LED_") (pin "C2") (pinfunction "C_C2") (pintype "passive"))
      (node (ref "U2") (pin "56") (pinfunction "PB4_56") (pintype "bidirectional"))
    )
    (net (code "48") (name "SWCLK") (class "Default")
      (node (ref "J3") (pin "4") (pinfunction "4_4") (pintype "passive"))
      (node (ref "U2") (pin "49") (pinfunction "SWCLK/PA14_49") (pintype "bidirectional"))
    )
    (net (code "49") (name "SWDIO") (class "Default")
      (node (ref "J3") (pin "2") (pinfunction "2_2") (pintype "passive"))
      (node (ref "U2") (pin "46") (pinfunction "SWDIO/PA13_46") (pintype "bidirectional"))
    )
    (net (code "50") (name "USB_DM") (class "Default")
      (node (ref "U2") (pin "44") (pinfunction "PA11_44") (pintype "bidirectional"))
      (node (ref "U3") (pin "6") (pinfunction "6_6") (pintype "bidirectional"))
    )
    (net (code "51") (name "USB_DP") (class "Default")
      (node (ref "U2") (pin "45") (pinfunction "PA12_45") (pintype "bidirectional"))
      (node (ref "U3") (pin "4") (pinfunction "4_4") (pintype "bidirectional"))
    )
    (net (code "52") (name "VARIANT0") (class "Default")
      (node (ref "R7") (pin "2") (pinfunction "2_2") (pintype "passive"))
      (node (ref "U2") (pin "53") (pinfunction "PC12_53") (pintype "bidirectional"))
    )
    (net (code "53") (name "VARIANT1") (class "Default")
      (node (ref "R8") (pin "2") (pinfunction "2_2") (pintype "passive"))
      (node (ref "U2") (pin "52") (pinfunction "PC11_52") (pintype "bidirectional"))
    )
    (net (code "54") (name "VBUS") (class "Default")
      (node (ref "F2") (pin "1") (pinfunction "1_1") (pintype "passive"))
      (node (ref "J2") (pin "A4/B9") (pinfunction "VBUS_A4/B9") (pintype "power_in"))
      (node (ref "J2") (pin "B4/A9") (pinfunction "VBUS_B4/A9") (pintype "power_in"))
      (node (ref "U3") (pin "5") (pinfunction "5_5") (pintype "passive"))
    )
    (net (code "55") (name "VCC") (class "Default")
      (node (ref "C11") (pin "2") (pinfunction "2_2") (pintype "passive"))
      (node (ref "C15") (pin "1") (pinfunction "1_1") (pintype "passive"))
      (node (ref "C16") (pin "1") (pinfunction "1_1") (pintype "passive"))
      (node (ref "C17") (pin "1") (pinfunction "1_1") (pintype "passive"))
      (node (ref "C18") (pin "1") (pinfunction "1_1") (pintype "passive"))
      (node (ref "C19") (pin "2") (pinfunction "2_2") (pintype "passive"))
      (node (ref "C2") (pin "2") (pinfunction "2_2") (pintype "passive"))
      (node (ref "C3") (pin "2") (pinfunction "2_2") (pintype "passive"))
      (node (ref "C4") (pin "2") (pinfunction "2_2") (pintype "passive"))
      (node (ref "C5") (pin "2") (pinfunction "2_2") (pintype "passive"))
      (node (ref "C9") (pin "2") (pinfunction "2_2") (pintype "passive"))
      (node (ref "J3") (pin "1") (pinfunction "1_1") (pintype "passive"))
      (node (ref "L1") (pin "P$2") (pinfunction "2_P$2") (pintype "passive"))
      (node (ref "L2") (pin "1") (pinfunction "1_1") (pintype "passive"))
      (node (ref "Q1") (pin "4") (pinfunction "VCC_4") (pintype "power_in"))
      (node (ref "R18") (pin "2") (pinfunction "2_2") (pintype "passive"))
      (node (ref "R19") (pin "2") (pinfunction "2_2") (pintype "passive"))
      (node (ref "SLAVEISOLATOR_1") (pin "1") (pinfunction "VDD1_1") (pintype "bidirectional"))
      (node (ref "SLAVEISOLATOR_11") (pin "1") (pinfunction "VDD1_1") (pintype "bidirectional"))
      (node (ref "SLAVEISOLATOR_12") (pin "8") (pinfunction "VDD2_8") (pintype "bidirectional"))
      (node (ref "SLAVEISOLATOR_2") (pin "8") (pinfunction "VDD2_8") (pintype "bidirectional"))
      (node (ref "U1") (pin "5") (pinfunction "FB_5") (pintype "input"))
      (node (ref "U2") (pin "1") (pinfunction "VBAT_1") (pintype "bidirectional"))
      (node (ref "U2") (pin "19") (pinfunction "VDD_19") (pintype "bidirectional"))
      (node (ref "U2") (pin "32") (pinfunction "VDD_32") (pintype "bidirectional"))
      (node (ref "U2") (pin "48") (pinfunction "VDD_48") (pintype "bidirectional"))
      (node (ref "U2") (pin "64") (pinfunction "VDD_64") (pintype "bidirectional"))
    )
    (net (code "56") (name "unconnected-(J2-SBU1-PadA8)") (class "Default")
      (node (ref "J2") (pin "A8") (pinfunction "SBU1_A8") (pintype "bidirectional"))
    )
    (net (code "57") (name "unconnected-(J2-SBU2-PadB8)") (class "Default")
      (node (ref "J2") (pin "B8") (pinfunction "SBU2_B8") (pintype "bidirectional"))
    )
    (net (code "58") (name "unconnected-(J3-Pad6)") (class "Default")
      (node (ref "J3") (pin "6") (pinfunction "6_6") (pintype "passive"))
    )
    (net (code "59") (name "unconnected-(J3-Pad7)") (class "Default")
      (node (ref "J3") (pin "7") (pinfunction "7_7") (pintype "passive"))
    )
    (net (code "60") (name "unconnected-(J3-Pad8)") (class "Default")
      (node (ref "J3") (pin "8") (pinfunction "8_8") (pintype "passive"))
    )
    (net (code "61") (name "unconnected-(J3-Pad9)") (class "Default")
      (node (ref "J3") (pin "9") (pinfunction "9_9") (pintype "passive"))
    )
    (net (code "62") (name "unconnected-(SLAVEISOLATOR_1-RCOUT-Pad7)") (class "Default")
      (node (ref "SLAVEISOLATOR_1") (pin "7") (pinfunction "RCOUT_7") (pintype "bidirectional"))
    )
    (net (code "63") (name "unconnected-(SLAVEISOLATOR_11-RCOUT-Pad7)") (class "Default")
      (node (ref "SLAVEISOLATOR_11") (pin "7") (pinfunction "RCOUT_7") (pintype "bidirectional"))
    )
    (net (code "64") (name "unconnected-(U2A-PA2-Pad16)") (class "Default")
      (node (ref "U2") (pin "16") (pinfunction "PA2_16") (pintype "bidirectional"))
    )
    (net (code "65") (name "unconnected-(U2A-PA3-Pad17)") (class "Default")
      (node (ref "U2") (pin "17") (pinfunction "PA3_17") (pintype "bidirectional"))
    )
    (net (code "66") (name "unconnected-(U2A-PA8-Pad41)") (class "Default")
      (node (ref "U2") (pin "41") (pinfunction "PA8_41") (pintype "bidirectional"))
    )
    (net (code "67") (name "unconnected-(U2A-PA9-Pad42)") (class "Default")
      (node (ref "U2") (pin "42") (pinfunction "PA9_42") (pintype "bidirectional"))
    )
    (net (code "68") (name "unconnected-(U2A-PA10-Pad43)") (class "Default")
      (node (ref "U2") (pin "43") (pinfunction "PA10_43") (pintype "bidirectional"))
    )
    (net (code "69") (name "unconnected-(U2A-PA15-Pad50)") (class "Default")
      (node (ref "U2") (pin "50") (pinfunction "PA15_50") (pintype "bidirectional"))
    )
    (net (code "70") (name "unconnected-(U2A-PB0-Pad26)") (class "Default")
      (node (ref "U2") (pin "26") (pinfunction "PB0_26") (pintype "bidirectional"))
    )
    (net (code "71") (name "unconnected-(U2A-PB1-Pad27)") (class "Default")
      (node (ref "U2") (pin "27") (pinfunction "PB1_27") (pintype "bidirectional"))
    )
    (net (code "72") (name "unconnected-(U2A-PB2{slash}BOOT1-Pad28)") (class "Default")
      (node (ref "U2") (pin "28") (pinfunction "PB2/BOOT1_28") (pintype "bidirectional"))
    )
    (net (code "73") (name "unconnected-(U2A-PB5-Pad57)") (class "Default")
      (node (ref "U2") (pin "57") (pinfunction "PB5_57") (pintype "bidirectional"))
    )
    (net (code "74") (name "unconnected-(U2A-PB6-Pad58)") (class "Default")
      (node (ref "U2") (pin "58") (pinfunction "PB6_58") (pintype "bidirectional"))
    )
    (net (code "75") (name "unconnected-(U2A-PB7-Pad59)") (class "Default")
      (node (ref "U2") (pin "59") (pinfunction "PB7_59") (pintype "bidirectional"))
    )
    (net (code "76") (name "unconnected-(U2A-PB8-Pad61)") (class "Default")
      (node (ref "U2") (pin "61") (pinfunction "PB8_61") (pintype "bidirectional"))
    )
    (net (code "77") (name "unconnected-(U2A-PB9-Pad62)") (class "Default")
      (node (ref "U2") (pin "62") (pinfunction "PB9_62") (pintype "bidirectional"))
    )
    (net (code "78") (name "unconnected-(U2A-PB10-Pad29)") (class "Default")
      (node (ref "U2") (pin "29") (pinfunction "PB10_29") (pintype "bidirectional"))
    )
    (net (code "79") (name "unconnected-(U2A-PC0-Pad8)") (class "Default")
      (node (ref "U2") (pin "8") (pinfunction "PC0_8") (pintype "bidirectional"))
    )
    (net (code "80") (name "unconnected-(U2A-PC1-Pad9)") (class "Default")
      (node (ref "U2") (pin "9") (pinfunction "PC1_9") (pintype "bidirectional"))
    )
    (net (code "81") (name "unconnected-(U2A-PC2-Pad10)") (class "Default")
      (node (ref "U2") (pin "10") (pinfunction "PC2_10") (pintype "bidirectional"))
    )
    (net (code "82") (name "unconnected-(U2A-PC3-Pad11)") (class "Default")
      (node (ref "U2") (pin "11") (pinfunction "PC3_11") (pintype "bidirectional"))
    )
    (net (code "83") (name "unconnected-(U2A-PC8-Pad39)") (class "Default")
      (node (ref "U2") (pin "39") (pinfunction "PC8_39") (pintype "bidirectional"))
    )
    (net (code "84") (name "unconnected-(U2A-PC9-Pad40)") (class "Default")
      (node (ref "U2") (pin "40") (pinfunction "PC9_40") (pintype "bidirectional"))
    )
    (net (code "85") (name "unconnected-(U2A-PC10-Pad51)") (class "Default")
      (node (ref "U2") (pin "51") (pinfunction "PC10_51") (pintype "bidirectional"))
    )
    (net (code "86") (name "unconnected-(U2A-PC13-Pad2)") (class "Default")
      (node (ref "U2") (pin "2") (pinfunction "PC13_2") (pintype "bidirectional"))
    )
    (net (code "87") (name "unconnected-(U2A-PC14{slash}OSC32_IN-Pad3)") (class "Default")
      (node (ref "U2") (pin "3") (pinfunction "PC14/OSC32_IN_3") (pintype "bidirectional"))
    )
    (net (code "88") (name "unconnected-(U2A-PC15{slash}OSC32_OUT-Pad4)") (class "Default")
      (node (ref "U2") (pin "4") (pinfunction "PC15/OSC32_OUT_4") (pintype "bidirectional"))
    )
    (net (code "89") (name "unconnected-(U2A-PD2-Pad54)") (class "Default")
      (node (ref "U2") (pin "54") (pinfunction "PD2_54") (pintype "bidirectional"))
    )
    (net (code "90") (name "unconnected-(U2A-PH1{slash}OSC_OUT-Pad6)") (class "Default")
      (node (ref "U2") (pin "6") (pinfunction "PH1/OSC_OUT_6") (pintype "bidirectional"))
    )
    (net (code "91") (name "~{NRST}") (class "Default")
      (node (ref "J3") (pin "10") (pinfunction "10_10") (pintype "passive"))
      (node (ref "U2") (pin "7") (pinfunction "NRST_7") (pintype "bidirectional"))
    )
  )
)
